# New_Schematic.net
KiCad netlist of a schematic drawn in EAGLE
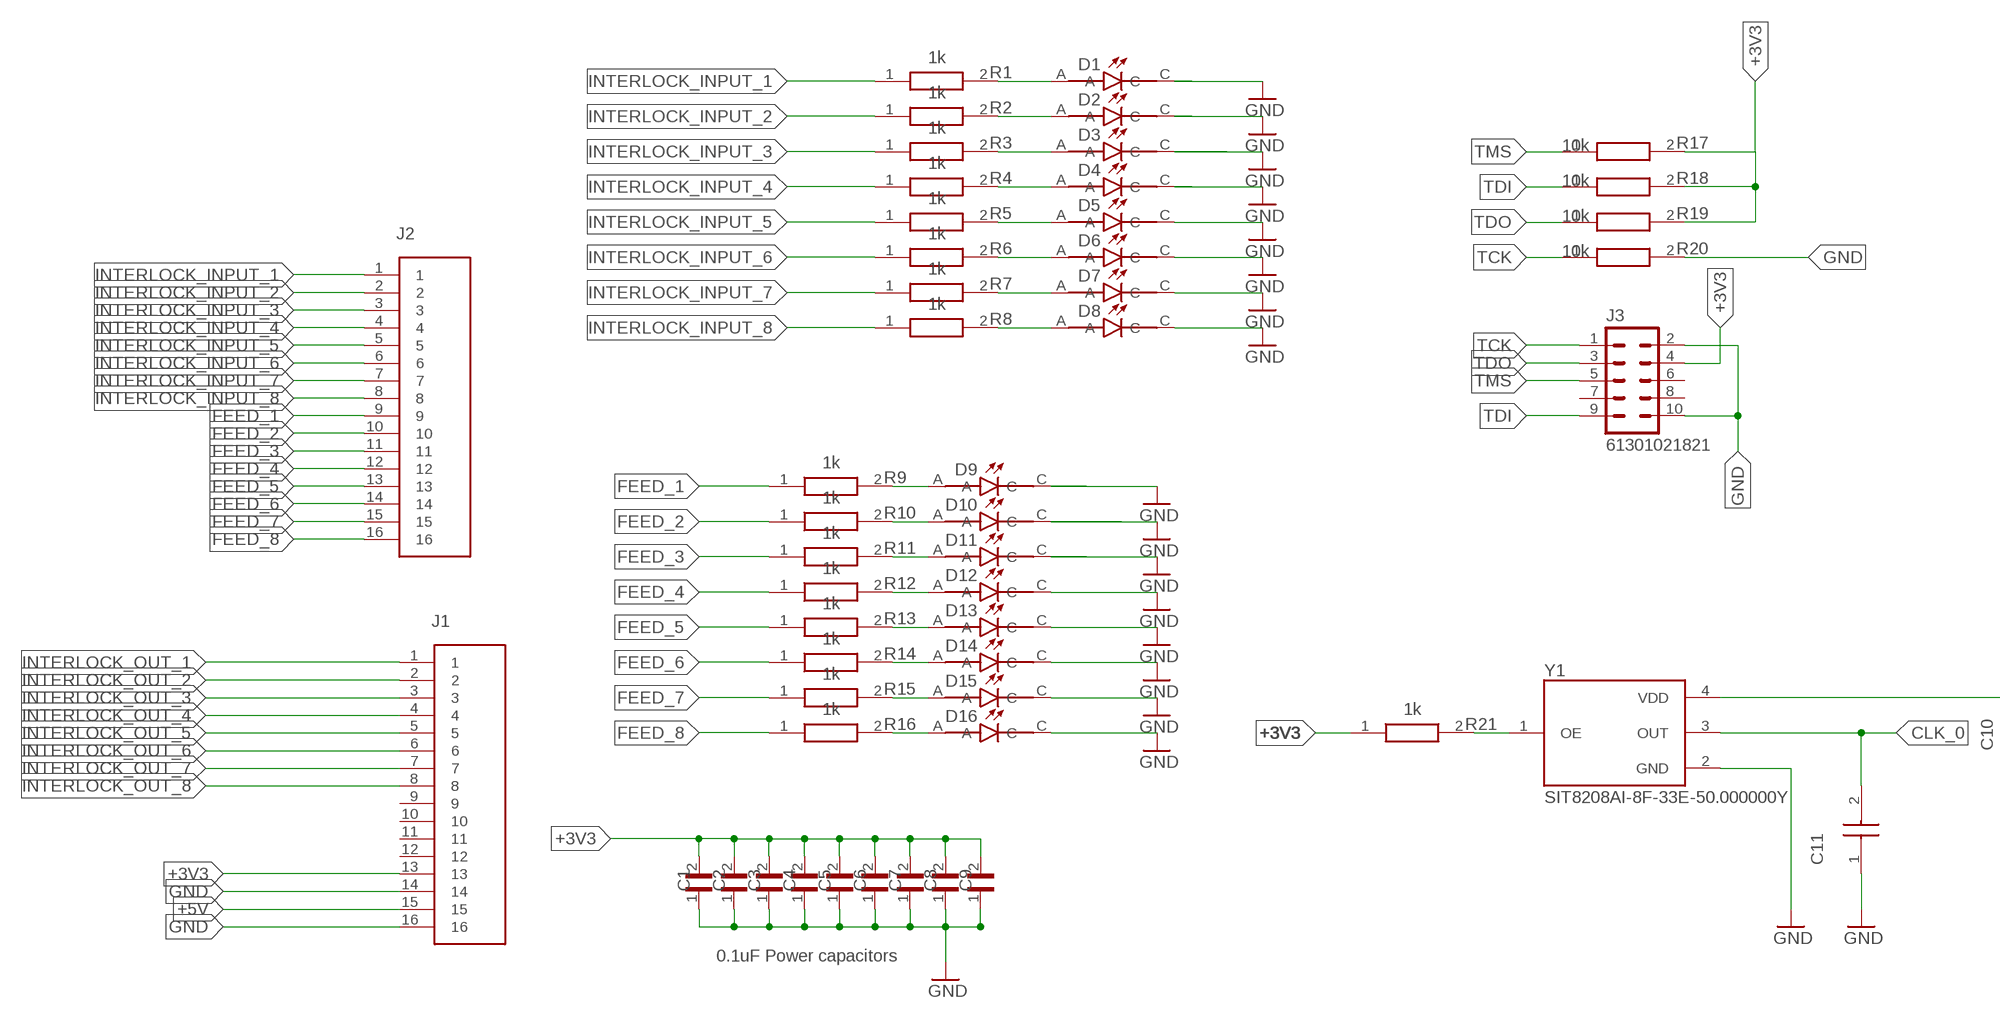
[diagram p0: schematic, sheet 1, part 1 of 2]
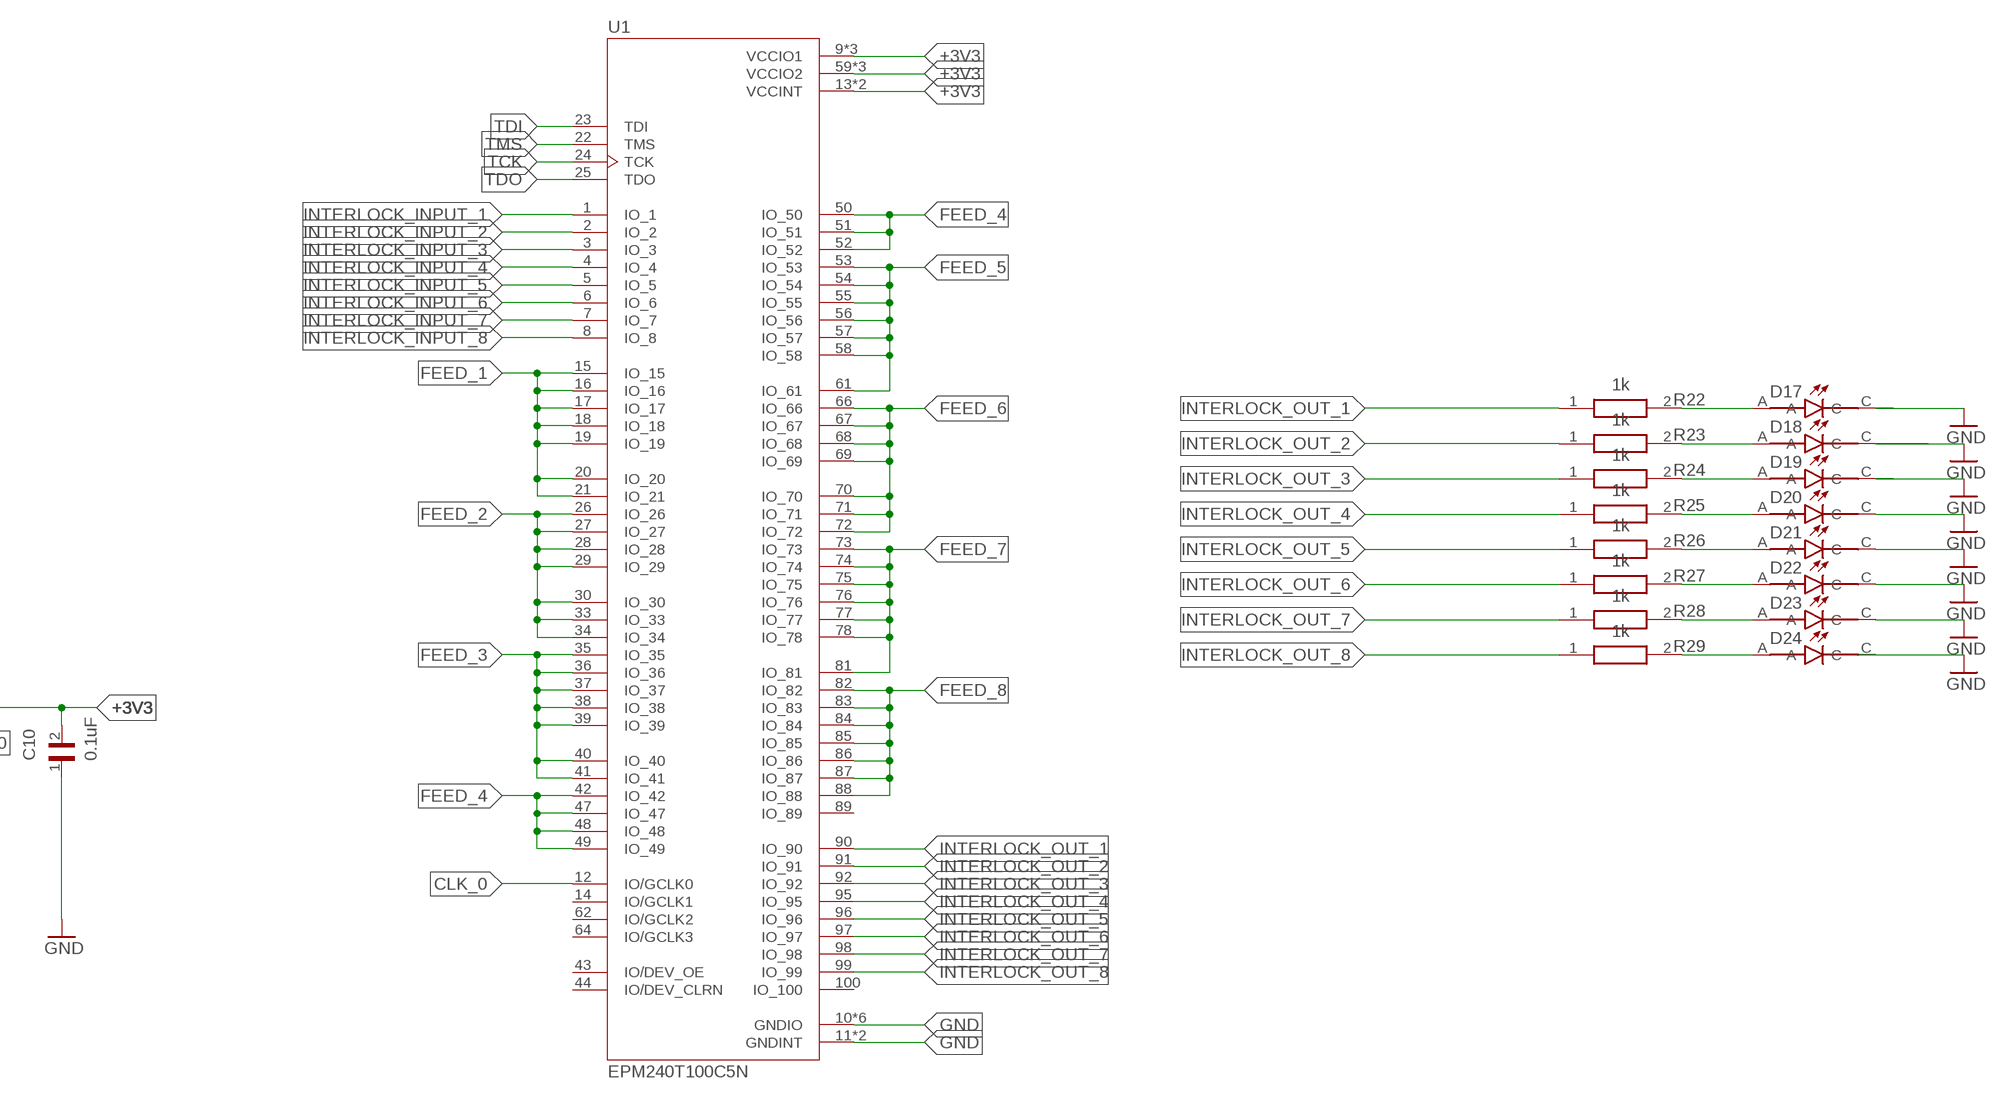
[diagram p1: schematic, sheet 1, part 2 of 2]

(export (version "E")
  (design (tool "Eeschema 10.0.6"))
  (components
    (comp (ref "C1")
      (value "GRM155R70J104KA01D")
      (footprint "eagle-import:CAPC1005X55N")
      (fields (field (name "DIGIKEY_PART_NUMBER") "490-6319-2-ND") (field (name "MF") "Murata"))
      (libsource (lib "eagle-import") (part "GRM155R70J104KA01D"))
    )
    (comp (ref "C2")
      (value "GRM155R70J104KA01D")
      (footprint "eagle-import:CAPC1005X55N")
      (fields (field (name "DIGIKEY_PART_NUMBER") "490-6319-2-ND") (field (name "MF") "Murata"))
      (libsource (lib "eagle-import") (part "GRM155R70J104KA01D"))
    )
    (comp (ref "C3")
      (value "GRM155R70J104KA01D")
      (footprint "eagle-import:CAPC1005X55N")
      (fields (field (name "DIGIKEY_PART_NUMBER") "490-6319-2-ND") (field (name "MF") "Murata"))
      (libsource (lib "eagle-import") (part "GRM155R70J104KA01D"))
    )
    (comp (ref "C4")
      (value "GRM155R70J104KA01D")
      (footprint "eagle-import:CAPC1005X55N")
      (fields (field (name "DIGIKEY_PART_NUMBER") "490-6319-2-ND") (field (name "MF") "Murata"))
      (libsource (lib "eagle-import") (part "GRM155R70J104KA01D"))
    )
    (comp (ref "C5")
      (value "GRM155R70J104KA01D")
      (footprint "eagle-import:CAPC1005X55N")
      (fields (field (name "DIGIKEY_PART_NUMBER") "490-6319-2-ND") (field (name "MF") "Murata"))
      (libsource (lib "eagle-import") (part "GRM155R70J104KA01D"))
    )
    (comp (ref "C6")
      (value "GRM155R70J104KA01D")
      (footprint "eagle-import:CAPC1005X55N")
      (fields (field (name "DIGIKEY_PART_NUMBER") "490-6319-2-ND") (field (name "MF") "Murata"))
      (libsource (lib "eagle-import") (part "GRM155R70J104KA01D"))
    )
    (comp (ref "C7")
      (value "GRM155R70J104KA01D")
      (footprint "eagle-import:CAPC1005X55N")
      (fields (field (name "DIGIKEY_PART_NUMBER") "490-6319-2-ND") (field (name "MF") "Murata"))
      (libsource (lib "eagle-import") (part "GRM155R70J104KA01D"))
    )
    (comp (ref "C8")
      (value "GRM155R70J104KA01D")
      (footprint "eagle-import:CAPC1005X55N")
      (fields (field (name "DIGIKEY_PART_NUMBER") "490-6319-2-ND") (field (name "MF") "Murata"))
      (libsource (lib "eagle-import") (part "GRM155R70J104KA01D"))
    )
    (comp (ref "C9")
      (value "GRM155R70J104KA01D")
      (footprint "eagle-import:CAPC1005X55N")
      (fields (field (name "DIGIKEY_PART_NUMBER") "490-6319-2-ND") (field (name "MF") "Murata"))
      (libsource (lib "eagle-import") (part "GRM155R70J104KA01D"))
    )
    (comp (ref "C10")
      (value "GRM155R70J104KA01D")
      (footprint "eagle-import:CAPC1005X55N")
      (fields
        (field (name "DIGIKEY_PART_NUMBER") "490-6319-2-ND")
        (field (name "MF") "Murata")
        (field (name "C10") "0.1uF")
      )
      (libsource (lib "eagle-import") (part "GRM155R70J104KA01D"))
    )
    (comp (ref "C11")
      (value "GRM1883U2A150JZ01B")
      (footprint "eagle-import:CAPC1608X90N")
      (libsource (lib "eagle-import") (part "GRM1883U2A150JZ01B"))
    )
    (comp (ref "D1")
      (value "HSMS-C190")
      (footprint "eagle-import:LEDM1608X80")
      (fields (field (name "MF") "Broadcom Limited"))
      (libsource (lib "eagle-import") (part "HSMS-C190"))
    )
    (comp (ref "D2")
      (value "HSMS-C190")
      (footprint "eagle-import:LEDM1608X80")
      (fields (field (name "MF") "Broadcom Limited"))
      (libsource (lib "eagle-import") (part "HSMS-C190"))
    )
    (comp (ref "D3")
      (value "HSMS-C190")
      (footprint "eagle-import:LEDM1608X80")
      (fields (field (name "MF") "Broadcom Limited"))
      (libsource (lib "eagle-import") (part "HSMS-C190"))
    )
    (comp (ref "D4")
      (value "HSMS-C190")
      (footprint "eagle-import:LEDM1608X80")
      (fields (field (name "MF") "Broadcom Limited"))
      (libsource (lib "eagle-import") (part "HSMS-C190"))
    )
    (comp (ref "D5")
      (value "HSMS-C190")
      (footprint "eagle-import:LEDM1608X80")
      (fields (field (name "MF") "Broadcom Limited"))
      (libsource (lib "eagle-import") (part "HSMS-C190"))
    )
    (comp (ref "D6")
      (value "HSMS-C190")
      (footprint "eagle-import:LEDM1608X80")
      (fields (field (name "MF") "Broadcom Limited"))
      (libsource (lib "eagle-import") (part "HSMS-C190"))
    )
    (comp (ref "D7")
      (value "HSMS-C190")
      (footprint "eagle-import:LEDM1608X80")
      (fields (field (name "MF") "Broadcom Limited"))
      (libsource (lib "eagle-import") (part "HSMS-C190"))
    )
    (comp (ref "D8")
      (value "HSMS-C190")
      (footprint "eagle-import:LEDM1608X80")
      (fields (field (name "MF") "Broadcom Limited"))
      (libsource (lib "eagle-import") (part "HSMS-C190"))
    )
    (comp (ref "D9")
      (value "HSMS-C190")
      (footprint "eagle-import:LEDM1608X80")
      (fields (field (name "MF") "Broadcom Limited"))
      (libsource (lib "eagle-import") (part "HSMS-C190"))
    )
    (comp (ref "D10")
      (value "HSMS-C190")
      (footprint "eagle-import:LEDM1608X80")
      (fields (field (name "MF") "Broadcom Limited"))
      (libsource (lib "eagle-import") (part "HSMS-C190"))
    )
    (comp (ref "D11")
      (value "HSMS-C190")
      (footprint "eagle-import:LEDM1608X80")
      (fields (field (name "MF") "Broadcom Limited"))
      (libsource (lib "eagle-import") (part "HSMS-C190"))
    )
    (comp (ref "D12")
      (value "HSMS-C190")
      (footprint "eagle-import:LEDM1608X80")
      (fields (field (name "MF") "Broadcom Limited"))
      (libsource (lib "eagle-import") (part "HSMS-C190"))
    )
    (comp (ref "D13")
      (value "HSMS-C190")
      (footprint "eagle-import:LEDM1608X80")
      (fields (field (name "MF") "Broadcom Limited"))
      (libsource (lib "eagle-import") (part "HSMS-C190"))
    )
    (comp (ref "D14")
      (value "HSMS-C190")
      (footprint "eagle-import:LEDM1608X80")
      (fields (field (name "MF") "Broadcom Limited"))
      (libsource (lib "eagle-import") (part "HSMS-C190"))
    )
    (comp (ref "D15")
      (value "HSMS-C190")
      (footprint "eagle-import:LEDM1608X80")
      (fields (field (name "MF") "Broadcom Limited"))
      (libsource (lib "eagle-import") (part "HSMS-C190"))
    )
    (comp (ref "D16")
      (value "HSMS-C190")
      (footprint "eagle-import:LEDM1608X80")
      (fields (field (name "MF") "Broadcom Limited"))
      (libsource (lib "eagle-import") (part "HSMS-C190"))
    )
    (comp (ref "D17")
      (value "HSMS-C190")
      (footprint "eagle-import:LEDM1608X80")
      (fields (field (name "MF") "Broadcom Limited"))
      (libsource (lib "eagle-import") (part "HSMS-C190"))
    )
    (comp (ref "D18")
      (value "HSMS-C190")
      (footprint "eagle-import:LEDM1608X80")
      (fields (field (name "MF") "Broadcom Limited"))
      (libsource (lib "eagle-import") (part "HSMS-C190"))
    )
    (comp (ref "D19")
      (value "HSMS-C190")
      (footprint "eagle-import:LEDM1608X80")
      (fields (field (name "MF") "Broadcom Limited"))
      (libsource (lib "eagle-import") (part "HSMS-C190"))
    )
    (comp (ref "D20")
      (value "HSMS-C190")
      (footprint "eagle-import:LEDM1608X80")
      (fields (field (name "MF") "Broadcom Limited"))
      (libsource (lib "eagle-import") (part "HSMS-C190"))
    )
    (comp (ref "D21")
      (value "HSMS-C190")
      (footprint "eagle-import:LEDM1608X80")
      (fields (field (name "MF") "Broadcom Limited"))
      (libsource (lib "eagle-import") (part "HSMS-C190"))
    )
    (comp (ref "D22")
      (value "HSMS-C190")
      (footprint "eagle-import:LEDM1608X80")
      (fields (field (name "MF") "Broadcom Limited"))
      (libsource (lib "eagle-import") (part "HSMS-C190"))
    )
    (comp (ref "D23")
      (value "HSMS-C190")
      (footprint "eagle-import:LEDM1608X80")
      (fields (field (name "MF") "Broadcom Limited"))
      (libsource (lib "eagle-import") (part "HSMS-C190"))
    )
    (comp (ref "D24")
      (value "HSMS-C190")
      (footprint "eagle-import:LEDM1608X80")
      (fields (field (name "MF") "Broadcom Limited"))
      (libsource (lib "eagle-import") (part "HSMS-C190"))
    )
    (comp (ref "J1")
      (value "1-2314812-6")
      (footprint "eagle-import:TE_1-2314812-6")
      (fields (field (name "DIGIKEY_PART_NUMBER") "17-1-2314812-6-ND") (field (name "MF") "TE Connectivity"))
      (libsource (lib "eagle-import") (part "1-2314812-6"))
    )
    (comp (ref "J2")
      (value "1-2314812-6")
      (footprint "eagle-import:TE_1-2314812-6")
      (fields (field (name "DIGIKEY_PART_NUMBER") "17-1-2314812-6-ND") (field (name "MF") "TE Connectivity"))
      (libsource (lib "eagle-import") (part "1-2314812-6"))
    )
    (comp (ref "J3")
      (value "61301021821")
      (footprint "eagle-import:2X05-PIN")
      (fields (field (name "MF") "Wurth Electronics"))
      (libsource (lib "eagle-import") (part "61301021821"))
    )
    (comp (ref "R1")
      (value "ERJS03D1001V")
      (footprint "eagle-import:RESC1608X55N")
      (fields (field (name "R1") "1k"))
      (libsource (lib "eagle-import") (part "ERJS03D1001V"))
    )
    (comp (ref "R2")
      (value "ERJS03D1001V")
      (footprint "eagle-import:RESC1608X55N")
      (fields (field (name "R1") "1k"))
      (libsource (lib "eagle-import") (part "ERJS03D1001V"))
    )
    (comp (ref "R3")
      (value "ERJS03D1001V")
      (footprint "eagle-import:RESC1608X55N")
      (fields (field (name "R1") "1k"))
      (libsource (lib "eagle-import") (part "ERJS03D1001V"))
    )
    (comp (ref "R4")
      (value "ERJS03D1001V")
      (footprint "eagle-import:RESC1608X55N")
      (fields (field (name "R1") "1k"))
      (libsource (lib "eagle-import") (part "ERJS03D1001V"))
    )
    (comp (ref "R5")
      (value "ERJS03D1001V")
      (footprint "eagle-import:RESC1608X55N")
      (fields (field (name "R1") "1k"))
      (libsource (lib "eagle-import") (part "ERJS03D1001V"))
    )
    (comp (ref "R6")
      (value "ERJS03D1001V")
      (footprint "eagle-import:RESC1608X55N")
      (fields (field (name "R1") "1k"))
      (libsource (lib "eagle-import") (part "ERJS03D1001V"))
    )
    (comp (ref "R7")
      (value "ERJS03D1001V")
      (footprint "eagle-import:RESC1608X55N")
      (fields (field (name "R1") "1k"))
      (libsource (lib "eagle-import") (part "ERJS03D1001V"))
    )
    (comp (ref "R8")
      (value "ERJS03D1001V")
      (footprint "eagle-import:RESC1608X55N")
      (fields (field (name "R1") "1k"))
      (libsource (lib "eagle-import") (part "ERJS03D1001V"))
    )
    (comp (ref "R9")
      (value "ERJS03D1001V")
      (footprint "eagle-import:RESC1608X55N")
      (fields (field (name "R1") "1k"))
      (libsource (lib "eagle-import") (part "ERJS03D1001V"))
    )
    (comp (ref "R10")
      (value "ERJS03D1001V")
      (footprint "eagle-import:RESC1608X55N")
      (fields (field (name "R1") "1k"))
      (libsource (lib "eagle-import") (part "ERJS03D1001V"))
    )
    (comp (ref "R11")
      (value "ERJS03D1001V")
      (footprint "eagle-import:RESC1608X55N")
      (fields (field (name "R1") "1k"))
      (libsource (lib "eagle-import") (part "ERJS03D1001V"))
    )
    (comp (ref "R12")
      (value "ERJS03D1001V")
      (footprint "eagle-import:RESC1608X55N")
      (fields (field (name "R1") "1k"))
      (libsource (lib "eagle-import") (part "ERJS03D1001V"))
    )
    (comp (ref "R13")
      (value "ERJS03D1001V")
      (footprint "eagle-import:RESC1608X55N")
      (fields (field (name "R1") "1k"))
      (libsource (lib "eagle-import") (part "ERJS03D1001V"))
    )
    (comp (ref "R14")
      (value "ERJS03D1001V")
      (footprint "eagle-import:RESC1608X55N")
      (fields (field (name "R1") "1k"))
      (libsource (lib "eagle-import") (part "ERJS03D1001V"))
    )
    (comp (ref "R15")
      (value "ERJS03D1001V")
      (footprint "eagle-import:RESC1608X55N")
      (fields (field (name "R1") "1k"))
      (libsource (lib "eagle-import") (part "ERJS03D1001V"))
    )
    (comp (ref "R16")
      (value "ERJS03D1001V")
      (footprint "eagle-import:RESC1608X55N")
      (fields (field (name "R1") "1k"))
      (libsource (lib "eagle-import") (part "ERJS03D1001V"))
    )
    (comp (ref "R17")
      (value "CRT0603-BY-1002EAS")
      (footprint "eagle-import:RESC1608X60N")
      (fields (field (name "MOUSER_PART_NUMBER") "652-CRT0603BY1002EAS") (field (name "R17") "10k"))
      (libsource (lib "eagle-import") (part "CRT0603-BY-1002EAS"))
    )
    (comp (ref "R18")
      (value "CRT0603-BY-1002EAS")
      (footprint "eagle-import:RESC1608X60N")
      (fields (field (name "MOUSER_PART_NUMBER") "652-CRT0603BY1002EAS") (field (name "R17") "10k"))
      (libsource (lib "eagle-import") (part "CRT0603-BY-1002EAS"))
    )
    (comp (ref "R19")
      (value "CRT0603-BY-1002EAS")
      (footprint "eagle-import:RESC1608X60N")
      (fields (field (name "MOUSER_PART_NUMBER") "652-CRT0603BY1002EAS") (field (name "R17") "10k"))
      (libsource (lib "eagle-import") (part "CRT0603-BY-1002EAS"))
    )
    (comp (ref "R20")
      (value "CRT0603-BY-1002EAS")
      (footprint "eagle-import:RESC1608X60N")
      (fields (field (name "MOUSER_PART_NUMBER") "652-CRT0603BY1002EAS") (field (name "R17") "10k"))
      (libsource (lib "eagle-import") (part "CRT0603-BY-1002EAS"))
    )
    (comp (ref "R21")
      (value "ERJS03D1001V")
      (footprint "eagle-import:RESC1608X55N")
      (fields (field (name "R1") "1k"))
      (libsource (lib "eagle-import") (part "ERJS03D1001V"))
    )
    (comp (ref "R22")
      (value "ERJS03D1001V")
      (footprint "eagle-import:RESC1608X55N")
      (fields (field (name "R1") "1k"))
      (libsource (lib "eagle-import") (part "ERJS03D1001V"))
    )
    (comp (ref "R23")
      (value "ERJS03D1001V")
      (footprint "eagle-import:RESC1608X55N")
      (fields (field (name "R1") "1k"))
      (libsource (lib "eagle-import") (part "ERJS03D1001V"))
    )
    (comp (ref "R24")
      (value "ERJS03D1001V")
      (footprint "eagle-import:RESC1608X55N")
      (fields (field (name "R1") "1k"))
      (libsource (lib "eagle-import") (part "ERJS03D1001V"))
    )
    (comp (ref "R25")
      (value "ERJS03D1001V")
      (footprint "eagle-import:RESC1608X55N")
      (fields (field (name "R1") "1k"))
      (libsource (lib "eagle-import") (part "ERJS03D1001V"))
    )
    (comp (ref "R26")
      (value "ERJS03D1001V")
      (footprint "eagle-import:RESC1608X55N")
      (fields (field (name "R1") "1k"))
      (libsource (lib "eagle-import") (part "ERJS03D1001V"))
    )
    (comp (ref "R27")
      (value "ERJS03D1001V")
      (footprint "eagle-import:RESC1608X55N")
      (fields (field (name "R1") "1k"))
      (libsource (lib "eagle-import") (part "ERJS03D1001V"))
    )
    (comp (ref "R28")
      (value "ERJS03D1001V")
      (footprint "eagle-import:RESC1608X55N")
      (fields (field (name "R1") "1k"))
      (libsource (lib "eagle-import") (part "ERJS03D1001V"))
    )
    (comp (ref "R29")
      (value "ERJS03D1001V")
      (footprint "eagle-import:RESC1608X55N")
      (fields (field (name "R1") "1k"))
      (libsource (lib "eagle-import") (part "ERJS03D1001V"))
    )
    (comp (ref "U1")
      (value "EPM240T100C5N")
      (footprint "eagle-import:QFP50P1600X1600X120-100N")
      (fields (field (name "DIGIKEY_PART_NUMBER") "544-1964-ND") (field (name "MF") "Intel"))
      (libsource (lib "eagle-import") (part "EPM240T100C5N"))
    )
    (comp (ref "Y1")
      (value "SIT8208AI-8F-33E-50.000000Y")
      (footprint "eagle-import:OSC_SIT8208AI-8F-33E-50.000000Y")
      (fields (field (name "MF") "SiTime"))
      (libsource (lib "eagle-import") (part "SIT8208AI-8F-33E-50.000000Y"))
    )
  )
  (nets
    (net (code "1") (name "+3V3") (class "Default")
      (node (ref "C1") (pin "2") (pinfunction "2_2") (pintype "passive"))
      (node (ref "C10") (pin "2") (pinfunction "2_2") (pintype "passive"))
      (node (ref "C2") (pin "2") (pinfunction "2_2") (pintype "passive"))
      (node (ref "C3") (pin "2") (pinfunction "2_2") (pintype "passive"))
      (node (ref "C4") (pin "2") (pinfunction "2_2") (pintype "passive"))
      (node (ref "C5") (pin "2") (pinfunction "2_2") (pintype "passive"))
      (node (ref "C6") (pin "2") (pinfunction "2_2") (pintype "passive"))
      (node (ref "C7") (pin "2") (pinfunction "2_2") (pintype "passive"))
      (node (ref "C8") (pin "2") (pinfunction "2_2") (pintype "passive"))
      (node (ref "C9") (pin "2") (pinfunction "2_2") (pintype "passive"))
      (node (ref "J1") (pin "13") (pinfunction "13_13") (pintype "passive"))
      (node (ref "J3") (pin "4") (pinfunction "4_4") (pintype "passive"))
      (node (ref "R17") (pin "2") (pinfunction "2_2") (pintype "bidirectional"))
      (node (ref "R18") (pin "2") (pinfunction "2_2") (pintype "bidirectional"))
      (node (ref "R19") (pin "2") (pinfunction "2_2") (pintype "bidirectional"))
      (node (ref "R21") (pin "1") (pinfunction "1_1") (pintype "bidirectional"))
      (node (ref "U1") (pin "13") (pinfunction "VCCINT_13") (pintype "power_in"))
      (node (ref "U1") (pin "31") (pinfunction "VCCIO1_31") (pintype "power_in"))
      (node (ref "U1") (pin "45") (pinfunction "VCCIO1_45") (pintype "power_in"))
      (node (ref "U1") (pin "59") (pinfunction "VCCIO2_59") (pintype "power_in"))
      (node (ref "U1") (pin "63") (pinfunction "VCCINT_63") (pintype "power_in"))
      (node (ref "U1") (pin "80") (pinfunction "VCCIO2_80") (pintype "power_in"))
      (node (ref "U1") (pin "9") (pinfunction "VCCIO1_9") (pintype "power_in"))
      (node (ref "U1") (pin "94") (pinfunction "VCCIO2_94") (pintype "power_in"))
      (node (ref "Y1") (pin "4") (pinfunction "VDD_4") (pintype "power_in"))
    )
    (net (code "2") (name "+5V") (class "Default")
      (node (ref "J1") (pin "15") (pinfunction "15_15") (pintype "passive"))
    )
    (net (code "3") (name "CLK_0") (class "Default")
      (node (ref "C11") (pin "2") (pinfunction "2_2") (pintype "bidirectional"))
      (node (ref "U1") (pin "12") (pinfunction "IO/GCLK0_12") (pintype "bidirectional"))
      (node (ref "Y1") (pin "3") (pinfunction "OUT_3") (pintype "output"))
    )
    (net (code "4") (name "FEED_1") (class "Default")
      (node (ref "J2") (pin "9") (pinfunction "9_9") (pintype "passive"))
      (node (ref "R9") (pin "1") (pinfunction "1_1") (pintype "bidirectional"))
      (node (ref "U1") (pin "15") (pinfunction "IO_15_15") (pintype "bidirectional"))
      (node (ref "U1") (pin "16") (pinfunction "IO_16_16") (pintype "bidirectional"))
      (node (ref "U1") (pin "17") (pinfunction "IO_17_17") (pintype "bidirectional"))
      (node (ref "U1") (pin "18") (pinfunction "IO_18_18") (pintype "bidirectional"))
      (node (ref "U1") (pin "19") (pinfunction "IO_19_19") (pintype "bidirectional"))
      (node (ref "U1") (pin "20") (pinfunction "IO_20_20") (pintype "bidirectional"))
      (node (ref "U1") (pin "21") (pinfunction "IO_21_21") (pintype "bidirectional"))
    )
    (net (code "5") (name "FEED_2") (class "Default")
      (node (ref "J2") (pin "10") (pinfunction "10_10") (pintype "passive"))
      (node (ref "R10") (pin "1") (pinfunction "1_1") (pintype "bidirectional"))
      (node (ref "U1") (pin "26") (pinfunction "IO_26_26") (pintype "bidirectional"))
      (node (ref "U1") (pin "27") (pinfunction "IO_27_27") (pintype "bidirectional"))
      (node (ref "U1") (pin "28") (pinfunction "IO_28_28") (pintype "bidirectional"))
      (node (ref "U1") (pin "29") (pinfunction "IO_29_29") (pintype "bidirectional"))
      (node (ref "U1") (pin "30") (pinfunction "IO_30_30") (pintype "bidirectional"))
      (node (ref "U1") (pin "33") (pinfunction "IO_33_33") (pintype "bidirectional"))
      (node (ref "U1") (pin "34") (pinfunction "IO_34_34") (pintype "bidirectional"))
    )
    (net (code "6") (name "FEED_3") (class "Default")
      (node (ref "J2") (pin "11") (pinfunction "11_11") (pintype "passive"))
      (node (ref "R11") (pin "1") (pinfunction "1_1") (pintype "bidirectional"))
      (node (ref "U1") (pin "35") (pinfunction "IO_35_35") (pintype "bidirectional"))
      (node (ref "U1") (pin "36") (pinfunction "IO_36_36") (pintype "bidirectional"))
      (node (ref "U1") (pin "37") (pinfunction "IO_37_37") (pintype "bidirectional"))
      (node (ref "U1") (pin "38") (pinfunction "IO_38_38") (pintype "bidirectional"))
      (node (ref "U1") (pin "39") (pinfunction "IO_39_39") (pintype "bidirectional"))
      (node (ref "U1") (pin "40") (pinfunction "IO_40_40") (pintype "bidirectional"))
      (node (ref "U1") (pin "41") (pinfunction "IO_41_41") (pintype "bidirectional"))
    )
    (net (code "7") (name "FEED_4") (class "Default")
      (node (ref "J2") (pin "12") (pinfunction "12_12") (pintype "passive"))
      (node (ref "R12") (pin "1") (pinfunction "1_1") (pintype "bidirectional"))
      (node (ref "U1") (pin "42") (pinfunction "IO_42_42") (pintype "bidirectional"))
      (node (ref "U1") (pin "47") (pinfunction "IO_47_47") (pintype "bidirectional"))
      (node (ref "U1") (pin "48") (pinfunction "IO_48_48") (pintype "bidirectional"))
      (node (ref "U1") (pin "49") (pinfunction "IO_49_49") (pintype "bidirectional"))
      (node (ref "U1") (pin "50") (pinfunction "IO_50_50") (pintype "bidirectional"))
      (node (ref "U1") (pin "51") (pinfunction "IO_51_51") (pintype "bidirectional"))
      (node (ref "U1") (pin "52") (pinfunction "IO_52_52") (pintype "bidirectional"))
    )
    (net (code "8") (name "FEED_5") (class "Default")
      (node (ref "J2") (pin "13") (pinfunction "13_13") (pintype "passive"))
      (node (ref "R13") (pin "1") (pinfunction "1_1") (pintype "bidirectional"))
      (node (ref "U1") (pin "53") (pinfunction "IO_53_53") (pintype "bidirectional"))
      (node (ref "U1") (pin "54") (pinfunction "IO_54_54") (pintype "bidirectional"))
      (node (ref "U1") (pin "55") (pinfunction "IO_55_55") (pintype "bidirectional"))
      (node (ref "U1") (pin "56") (pinfunction "IO_56_56") (pintype "bidirectional"))
      (node (ref "U1") (pin "57") (pinfunction "IO_57_57") (pintype "bidirectional"))
      (node (ref "U1") (pin "58") (pinfunction "IO_58_58") (pintype "bidirectional"))
      (node (ref "U1") (pin "61") (pinfunction "IO_61_61") (pintype "bidirectional"))
    )
    (net (code "9") (name "FEED_6") (class "Default")
      (node (ref "J2") (pin "14") (pinfunction "14_14") (pintype "passive"))
      (node (ref "R14") (pin "1") (pinfunction "1_1") (pintype "bidirectional"))
      (node (ref "U1") (pin "66") (pinfunction "IO_66_66") (pintype "bidirectional"))
      (node (ref "U1") (pin "67") (pinfunction "IO_67_67") (pintype "bidirectional"))
      (node (ref "U1") (pin "68") (pinfunction "IO_68_68") (pintype "bidirectional"))
      (node (ref "U1") (pin "69") (pinfunction "IO_69_69") (pintype "bidirectional"))
      (node (ref "U1") (pin "70") (pinfunction "IO_70_70") (pintype "bidirectional"))
      (node (ref "U1") (pin "71") (pinfunction "IO_71_71") (pintype "bidirectional"))
      (node (ref "U1") (pin "72") (pinfunction "IO_72_72") (pintype "bidirectional"))
    )
    (net (code "10") (name "FEED_7") (class "Default")
      (node (ref "J2") (pin "15") (pinfunction "15_15") (pintype "passive"))
      (node (ref "R15") (pin "1") (pinfunction "1_1") (pintype "bidirectional"))
      (node (ref "U1") (pin "73") (pinfunction "IO_73_73") (pintype "bidirectional"))
      (node (ref "U1") (pin "74") (pinfunction "IO_74_74") (pintype "bidirectional"))
      (node (ref "U1") (pin "75") (pinfunction "IO_75_75") (pintype "bidirectional"))
      (node (ref "U1") (pin "76") (pinfunction "IO_76_76") (pintype "bidirectional"))
      (node (ref "U1") (pin "77") (pinfunction "IO_77_77") (pintype "bidirectional"))
      (node (ref "U1") (pin "78") (pinfunction "IO_78_78") (pintype "bidirectional"))
      (node (ref "U1") (pin "81") (pinfunction "IO_81_81") (pintype "bidirectional"))
    )
    (net (code "11") (name "FEED_8") (class "Default")
      (node (ref "J2") (pin "16") (pinfunction "16_16") (pintype "passive"))
      (node (ref "R16") (pin "1") (pinfunction "1_1") (pintype "bidirectional"))
      (node (ref "U1") (pin "82") (pinfunction "IO_82_82") (pintype "bidirectional"))
      (node (ref "U1") (pin "83") (pinfunction "IO_83_83") (pintype "bidirectional"))
      (node (ref "U1") (pin "84") (pinfunction "IO_84_84") (pintype "bidirectional"))
      (node (ref "U1") (pin "85") (pinfunction "IO_85_85") (pintype "bidirectional"))
      (node (ref "U1") (pin "86") (pinfunction "IO_86_86") (pintype "bidirectional"))
      (node (ref "U1") (pin "87") (pinfunction "IO_87_87") (pintype "bidirectional"))
      (node (ref "U1") (pin "88") (pinfunction "IO_88_88") (pintype "bidirectional"))
    )
    (net (code "12") (name "GND") (class "Default")
      (node (ref "C1") (pin "1") (pinfunction "1_1") (pintype "passive"))
      (node (ref "C10") (pin "1") (pinfunction "1_1") (pintype "passive"))
      (node (ref "C11") (pin "1") (pinfunction "1_1") (pintype "bidirectional"))
      (node (ref "C2") (pin "1") (pinfunction "1_1") (pintype "passive"))
      (node (ref "C3") (pin "1") (pinfunction "1_1") (pintype "passive"))
      (node (ref "C4") (pin "1") (pinfunction "1_1") (pintype "passive"))
      (node (ref "C5") (pin "1") (pinfunction "1_1") (pintype "passive"))
      (node (ref "C6") (pin "1") (pinfunction "1_1") (pintype "passive"))
      (node (ref "C7") (pin "1") (pinfunction "1_1") (pintype "passive"))
      (node (ref "C8") (pin "1") (pinfunction "1_1") (pintype "passive"))
      (node (ref "C9") (pin "1") (pinfunction "1_1") (pintype "passive"))
      (node (ref "D1") (pin "C") (pinfunction "C_C") (pintype "passive"))
      (node (ref "D10") (pin "C") (pinfunction "C_C") (pintype "passive"))
      (node (ref "D11") (pin "C") (pinfunction "C_C") (pintype "passive"))
      (node (ref "D12") (pin "C") (pinfunction "C_C") (pintype "passive"))
      (node (ref "D13") (pin "C") (pinfunction "C_C") (pintype "passive"))
      (node (ref "D14") (pin "C") (pinfunction "C_C") (pintype "passive"))
      (node (ref "D15") (pin "C") (pinfunction "C_C") (pintype "passive"))
      (node (ref "D16") (pin "C") (pinfunction "C_C") (pintype "passive"))
      (node (ref "D17") (pin "C") (pinfunction "C_C") (pintype "passive"))
      (node (ref "D18") (pin "C") (pinfunction "C_C") (pintype "passive"))
      (node (ref "D19") (pin "C") (pinfunction "C_C") (pintype "passive"))
      (node (ref "D2") (pin "C") (pinfunction "C_C") (pintype "passive"))
      (node (ref "D20") (pin "C") (pinfunction "C_C") (pintype "passive"))
      (node (ref "D21") (pin "C") (pinfunction "C_C") (pintype "passive"))
      (node (ref "D22") (pin "C") (pinfunction "C_C") (pintype "passive"))
      (node (ref "D23") (pin "C") (pinfunction "C_C") (pintype "passive"))
      (node (ref "D24") (pin "C") (pinfunction "C_C") (pintype "passive"))
      (node (ref "D3") (pin "C") (pinfunction "C_C") (pintype "passive"))
      (node (ref "D4") (pin "C") (pinfunction "C_C") (pintype "passive"))
      (node (ref "D5") (pin "C") (pinfunction "C_C") (pintype "passive"))
      (node (ref "D6") (pin "C") (pinfunction "C_C") (pintype "passive"))
      (node (ref "D7") (pin "C") (pinfunction "C_C") (pintype "passive"))
      (node (ref "D8") (pin "C") (pinfunction "C_C") (pintype "passive"))
      (node (ref "D9") (pin "C") (pinfunction "C_C") (pintype "passive"))
      (node (ref "J1") (pin "14") (pinfunction "14_14") (pintype "passive"))
      (node (ref "J1") (pin "16") (pinfunction "16_16") (pintype "passive"))
      (node (ref "J3") (pin "10") (pinfunction "10_10") (pintype "passive"))
      (node (ref "J3") (pin "2") (pinfunction "2_2") (pintype "passive"))
      (node (ref "R20") (pin "2") (pinfunction "2_2") (pintype "bidirectional"))
      (node (ref "U1") (pin "10") (pinfunction "GNDIO_10") (pintype "power_in"))
      (node (ref "U1") (pin "11") (pinfunction "GNDINT_11") (pintype "power_in"))
      (node (ref "U1") (pin "32") (pinfunction "GNDIO_32") (pintype "power_in"))
      (node (ref "U1") (pin "46") (pinfunction "GNDIO_46") (pintype "power_in"))
      (node (ref "U1") (pin "60") (pinfunction "GNDIO_60") (pintype "power_in"))
      (node (ref "U1") (pin "65") (pinfunction "GNDINT_65") (pintype "power_in"))
      (node (ref "U1") (pin "79") (pinfunction "GNDIO_79") (pintype "power_in"))
      (node (ref "U1") (pin "93") (pinfunction "GNDIO_93") (pintype "power_in"))
      (node (ref "Y1") (pin "2") (pinfunction "GND_2") (pintype "power_in"))
    )
    (net (code "13") (name "INTERLOCK_INPUT_1") (class "Default")
      (node (ref "J2") (pin "1") (pinfunction "1_1") (pintype "passive"))
      (node (ref "R1") (pin "1") (pinfunction "1_1") (pintype "bidirectional"))
      (node (ref "U1") (pin "1") (pinfunction "IO_1_1") (pintype "bidirectional"))
    )
    (net (code "14") (name "INTERLOCK_INPUT_2") (class "Default")
      (node (ref "J2") (pin "2") (pinfunction "2_2") (pintype "passive"))
      (node (ref "R2") (pin "1") (pinfunction "1_1") (pintype "bidirectional"))
      (node (ref "U1") (pin "2") (pinfunction "IO_2_2") (pintype "bidirectional"))
    )
    (net (code "15") (name "INTERLOCK_INPUT_3") (class "Default")
      (node (ref "J2") (pin "3") (pinfunction "3_3") (pintype "passive"))
      (node (ref "R3") (pin "1") (pinfunction "1_1") (pintype "bidirectional"))
      (node (ref "U1") (pin "3") (pinfunction "IO_3_3") (pintype "bidirectional"))
    )
    (net (code "16") (name "INTERLOCK_INPUT_4") (class "Default")
      (node (ref "J2") (pin "4") (pinfunction "4_4") (pintype "passive"))
      (node (ref "R4") (pin "1") (pinfunction "1_1") (pintype "bidirectional"))
      (node (ref "U1") (pin "4") (pinfunction "IO_4_4") (pintype "bidirectional"))
    )
    (net (code "17") (name "INTERLOCK_INPUT_5") (class "Default")
      (node (ref "J2") (pin "5") (pinfunction "5_5") (pintype "passive"))
      (node (ref "R5") (pin "1") (pinfunction "1_1") (pintype "bidirectional"))
      (node (ref "U1") (pin "5") (pinfunction "IO_5_5") (pintype "bidirectional"))
    )
    (net (code "18") (name "INTERLOCK_INPUT_6") (class "Default")
      (node (ref "J2") (pin "6") (pinfunction "6_6") (pintype "passive"))
      (node (ref "R6") (pin "1") (pinfunction "1_1") (pintype "bidirectional"))
      (node (ref "U1") (pin "6") (pinfunction "IO_6_6") (pintype "bidirectional"))
    )
    (net (code "19") (name "INTERLOCK_INPUT_7") (class "Default")
      (node (ref "J2") (pin "7") (pinfunction "7_7") (pintype "passive"))
      (node (ref "R7") (pin "1") (pinfunction "1_1") (pintype "bidirectional"))
      (node (ref "U1") (pin "7") (pinfunction "IO_7_7") (pintype "bidirectional"))
    )
    (net (code "20") (name "INTERLOCK_INPUT_8") (class "Default")
      (node (ref "J2") (pin "8") (pinfunction "8_8") (pintype "passive"))
      (node (ref "R8") (pin "1") (pinfunction "1_1") (pintype "bidirectional"))
      (node (ref "U1") (pin "8") (pinfunction "IO_8_8") (pintype "bidirectional"))
    )
    (net (code "21") (name "INTERLOCK_OUT_1") (class "Default")
      (node (ref "J1") (pin "1") (pinfunction "1_1") (pintype "passive"))
      (node (ref "R22") (pin "1") (pinfunction "1_1") (pintype "bidirectional"))
      (node (ref "U1") (pin "90") (pinfunction "IO_90_90") (pintype "bidirectional"))
    )
    (net (code "22") (name "INTERLOCK_OUT_2") (class "Default")
      (node (ref "J1") (pin "2") (pinfunction "2_2") (pintype "passive"))
      (node (ref "R23") (pin "1") (pinfunction "1_1") (pintype "bidirectional"))
      (node (ref "U1") (pin "91") (pinfunction "IO_91_91") (pintype "bidirectional"))
    )
    (net (code "23") (name "INTERLOCK_OUT_3") (class "Default")
      (node (ref "J1") (pin "3") (pinfunction "3_3") (pintype "passive"))
      (node (ref "R24") (pin "1") (pinfunction "1_1") (pintype "bidirectional"))
      (node (ref "U1") (pin "92") (pinfunction "IO_92_92") (pintype "bidirectional"))
    )
    (net (code "24") (name "INTERLOCK_OUT_4") (class "Default")
      (node (ref "J1") (pin "4") (pinfunction "4_4") (pintype "passive"))
      (node (ref "R25") (pin "1") (pinfunction "1_1") (pintype "bidirectional"))
      (node (ref "U1") (pin "95") (pinfunction "IO_95_95") (pintype "bidirectional"))
    )
    (net (code "25") (name "INTERLOCK_OUT_5") (class "Default")
      (node (ref "J1") (pin "5") (pinfunction "5_5") (pintype "passive"))
      (node (ref "R26") (pin "1") (pinfunction "1_1") (pintype "bidirectional"))
      (node (ref "U1") (pin "96") (pinfunction "IO_96_96") (pintype "bidirectional"))
    )
    (net (code "26") (name "INTERLOCK_OUT_6") (class "Default")
      (node (ref "J1") (pin "6") (pinfunction "6_6") (pintype "passive"))
      (node (ref "R27") (pin "1") (pinfunction "1_1") (pintype "bidirectional"))
      (node (ref "U1") (pin "97") (pinfunction "IO_97_97") (pintype "bidirectional"))
    )
    (net (code "27") (name "INTERLOCK_OUT_7") (class "Default")
      (node (ref "J1") (pin "7") (pinfunction "7_7") (pintype "passive"))
      (node (ref "R28") (pin "1") (pinfunction "1_1") (pintype "bidirectional"))
      (node (ref "U1") (pin "98") (pinfunction "IO_98_98") (pintype "bidirectional"))
    )
    (net (code "28") (name "INTERLOCK_OUT_8") (class "Default")
      (node (ref "J1") (pin "8") (pinfunction "8_8") (pintype "passive"))
      (node (ref "R29") (pin "1") (pinfunction "1_1") (pintype "bidirectional"))
      (node (ref "U1") (pin "99") (pinfunction "IO_99_99") (pintype "bidirectional"))
    )
    (net (code "29") (name "Net-(D1-PadA)") (class "Default")
      (node (ref "D1") (pin "A") (pinfunction "A_A") (pintype "passive"))
      (node (ref "R1") (pin "2") (pinfunction "2_2") (pintype "bidirectional"))
    )
    (net (code "30") (name "Net-(D2-PadA)") (class "Default")
      (node (ref "D2") (pin "A") (pinfunction "A_A") (pintype "passive"))
      (node (ref "R2") (pin "2") (pinfunction "2_2") (pintype "bidirectional"))
    )
    (net (code "31") (name "Net-(D3-PadA)") (class "Default")
      (node (ref "D3") (pin "A") (pinfunction "A_A") (pintype "passive"))
      (node (ref "R3") (pin "2") (pinfunction "2_2") (pintype "bidirectional"))
    )
    (net (code "32") (name "Net-(D4-PadA)") (class "Default")
      (node (ref "D4") (pin "A") (pinfunction "A_A") (pintype "passive"))
      (node (ref "R4") (pin "2") (pinfunction "2_2") (pintype "bidirectional"))
    )
    (net (code "33") (name "Net-(D5-PadA)") (class "Default")
      (node (ref "D5") (pin "A") (pinfunction "A_A") (pintype "passive"))
      (node (ref "R5") (pin "2") (pinfunction "2_2") (pintype "bidirectional"))
    )
    (net (code "34") (name "Net-(D6-PadA)") (class "Default")
      (node (ref "D6") (pin "A") (pinfunction "A_A") (pintype "passive"))
      (node (ref "R6") (pin "2") (pinfunction "2_2") (pintype "bidirectional"))
    )
    (net (code "35") (name "Net-(D7-PadA)") (class "Default")
      (node (ref "D7") (pin "A") (pinfunction "A_A") (pintype "passive"))
      (node (ref "R7") (pin "2") (pinfunction "2_2") (pintype "bidirectional"))
    )
    (net (code "36") (name "Net-(D8-PadA)") (class "Default")
      (node (ref "D8") (pin "A") (pinfunction "A_A") (pintype "passive"))
      (node (ref "R8") (pin "2") (pinfunction "2_2") (pintype "bidirectional"))
    )
    (net (code "37") (name "Net-(D9-PadA)") (class "Default")
      (node (ref "D9") (pin "A") (pinfunction "A_A") (pintype "passive"))
      (node (ref "R9") (pin "2") (pinfunction "2_2") (pintype "bidirectional"))
    )
    (net (code "38") (name "Net-(D10-PadA)") (class "Default")
      (node (ref "D10") (pin "A") (pinfunction "A_A") (pintype "passive"))
      (node (ref "R10") (pin "2") (pinfunction "2_2") (pintype "bidirectional"))
    )
    (net (code "39") (name "Net-(D11-PadA)") (class "Default")
      (node (ref "D11") (pin "A") (pinfunction "A_A") (pintype "passive"))
      (node (ref "R11") (pin "2") (pinfunction "2_2") (pintype "bidirectional"))
    )
    (net (code "40") (name "Net-(D12-PadA)") (class "Default")
      (node (ref "D12") (pin "A") (pinfunction "A_A") (pintype "passive"))
      (node (ref "R12") (pin "2") (pinfunction "2_2") (pintype "bidirectional"))
    )
    (net (code "41") (name "Net-(D13-PadA)") (class "Default")
      (node (ref "D13") (pin "A") (pinfunction "A_A") (pintype "passive"))
      (node (ref "R13") (pin "2") (pinfunction "2_2") (pintype "bidirectional"))
    )
    (net (code "42") (name "Net-(D14-PadA)") (class "Default")
      (node (ref "D14") (pin "A") (pinfunction "A_A") (pintype "passive"))
      (node (ref "R14") (pin "2") (pinfunction "2_2") (pintype "bidirectional"))
    )
    (net (code "43") (name "Net-(D15-PadA)") (class "Default")
      (node (ref "D15") (pin "A") (pinfunction "A_A") (pintype "passive"))
      (node (ref "R15") (pin "2") (pinfunction "2_2") (pintype "bidirectional"))
    )
    (net (code "44") (name "Net-(D16-PadA)") (class "Default")
      (node (ref "D16") (pin "A") (pinfunction "A_A") (pintype "passive"))
      (node (ref "R16") (pin "2") (pinfunction "2_2") (pintype "bidirectional"))
    )
    (net (code "45") (name "Net-(D17-PadA)") (class "Default")
      (node (ref "D17") (pin "A") (pinfunction "A_A") (pintype "passive"))
      (node (ref "R22") (pin "2") (pinfunction "2_2") (pintype "bidirectional"))
    )
    (net (code "46") (name "Net-(D18-PadA)") (class "Default")
      (node (ref "D18") (pin "A") (pinfunction "A_A") (pintype "passive"))
      (node (ref "R23") (pin "2") (pinfunction "2_2") (pintype "bidirectional"))
    )
    (net (code "47") (name "Net-(D19-PadA)") (class "Default")
      (node (ref "D19") (pin "A") (pinfunction "A_A") (pintype "passive"))
      (node (ref "R24") (pin "2") (pinfunction "2_2") (pintype "bidirectional"))
    )
    (net (code "48") (name "Net-(D20-PadA)") (class "Default")
      (node (ref "D20") (pin "A") (pinfunction "A_A") (pintype "passive"))
      (node (ref "R25") (pin "2") (pinfunction "2_2") (pintype "bidirectional"))
    )
    (net (code "49") (name "Net-(D21-PadA)") (class "Default")
      (node (ref "D21") (pin "A") (pinfunction "A_A") (pintype "passive"))
      (node (ref "R26") (pin "2") (pinfunction "2_2") (pintype "bidirectional"))
    )
    (net (code "50") (name "Net-(D22-PadA)") (class "Default")
      (node (ref "D22") (pin "A") (pinfunction "A_A") (pintype "passive"))
      (node (ref "R27") (pin "2") (pinfunction "2_2") (pintype "bidirectional"))
    )
    (net (code "51") (name "Net-(D23-PadA)") (class "Default")
      (node (ref "D23") (pin "A") (pinfunction "A_A") (pintype "passive"))
      (node (ref "R28") (pin "2") (pinfunction "2_2") (pintype "bidirectional"))
    )
    (net (code "52") (name "Net-(D24-PadA)") (class "Default")
      (node (ref "D24") (pin "A") (pinfunction "A_A") (pintype "passive"))
      (node (ref "R29") (pin "2") (pinfunction "2_2") (pintype "bidirectional"))
    )
    (net (code "53") (name "Net-(Y1-OE)") (class "Default")
      (node (ref "R21") (pin "2") (pinfunction "2_2") (pintype "bidirectional"))
      (node (ref "Y1") (pin "1") (pinfunction "OE_1") (pintype "input"))
    )
    (net (code "54") (name "TCK") (class "Default")
      (node (ref "J3") (pin "1") (pinfunction "1_1") (pintype "passive"))
      (node (ref "R20") (pin "1") (pinfunction "1_1") (pintype "bidirectional"))
      (node (ref "U1") (pin "24") (pinfunction "TCK_24") (pintype "input"))
    )
    (net (code "55") (name "TDI") (class "Default")
      (node (ref "J3") (pin "9") (pinfunction "9_9") (pintype "passive"))
      (node (ref "R18") (pin "1") (pinfunction "1_1") (pintype "bidirectional"))
      (node (ref "U1") (pin "23") (pinfunction "TDI_23") (pintype "input"))
    )
    (net (code "56") (name "TDO") (class "Default")
      (node (ref "J3") (pin "3") (pinfunction "3_3") (pintype "passive"))
      (node (ref "R19") (pin "1") (pinfunction "1_1") (pintype "bidirectional"))
      (node (ref "U1") (pin "25") (pinfunction "TDO_25") (pintype "output"))
    )
    (net (code "57") (name "TMS") (class "Default")
      (node (ref "J3") (pin "5") (pinfunction "5_5") (pintype "passive"))
      (node (ref "R17") (pin "1") (pinfunction "1_1") (pintype "bidirectional"))
      (node (ref "U1") (pin "22") (pinfunction "TMS_22") (pintype "input"))
    )
    (net (code "58") (name "unconnected-(J1-Pad9)") (class "Default")
      (node (ref "J1") (pin "9") (pinfunction "9_9") (pintype "passive"))
    )
    (net (code "59") (name "unconnected-(J1-Pad10)") (class "Default")
      (node (ref "J1") (pin "10") (pinfunction "10_10") (pintype "passive"))
    )
    (net (code "60") (name "unconnected-(J1-Pad11)") (class "Default")
      (node (ref "J1") (pin "11") (pinfunction "11_11") (pintype "passive"))
    )
    (net (code "61") (name "unconnected-(J1-Pad12)") (class "Default")
      (node (ref "J1") (pin "12") (pinfunction "12_12") (pintype "passive"))
    )
    (net (code "62") (name "unconnected-(J3-Pad6)") (class "Default")
      (node (ref "J3") (pin "6") (pinfunction "6_6") (pintype "passive"))
    )
    (net (code "63") (name "unconnected-(J3-Pad7)") (class "Default")
      (node (ref "J3") (pin "7") (pinfunction "7_7") (pintype "passive"))
    )
    (net (code "64") (name "unconnected-(J3-Pad8)") (class "Default")
      (node (ref "J3") (pin "8") (pinfunction "8_8") (pintype "passive"))
    )
    (net (code "65") (name "unconnected-(U1-IO_89-Pad89)") (class "Default")
      (node (ref "U1") (pin "89") (pinfunction "IO_89_89") (pintype "bidirectional"))
    )
    (net (code "66") (name "unconnected-(U1-IO_100-Pad100)") (class "Default")
      (node (ref "U1") (pin "100") (pinfunction "IO_100_100") (pintype "bidirectional"))
    )
    (net (code "67") (name "unconnected-(U1-IO{slash}DEV_CLRN-Pad44)") (class "Default")
      (node (ref "U1") (pin "44") (pinfunction "IO/DEV_CLRN_44") (pintype "bidirectional"))
    )
    (net (code "68") (name "unconnected-(U1-IO{slash}DEV_OE-Pad43)") (class "Default")
      (node (ref "U1") (pin "43") (pinfunction "IO/DEV_OE_43") (pintype "bidirectional"))
    )
    (net (code "69") (name "unconnected-(U1-IO{slash}GCLK1-Pad14)") (class "Default")
      (node (ref "U1") (pin "14") (pinfunction "IO/GCLK1_14") (pintype "bidirectional"))
    )
    (net (code "70") (name "unconnected-(U1-IO{slash}GCLK2-Pad62)") (class "Default")
      (node (ref "U1") (pin "62") (pinfunction "IO/GCLK2_62") (pintype "bidirectional"))
    )
    (net (code "71") (name "unconnected-(U1-IO{slash}GCLK3-Pad64)") (class "Default")
      (node (ref "U1") (pin "64") (pinfunction "IO/GCLK3_64") (pintype "bidirectional"))
    )
  )
)
